# PAGE1-Power.net
KiCad netlist of a schematic drawn in Altium Designer
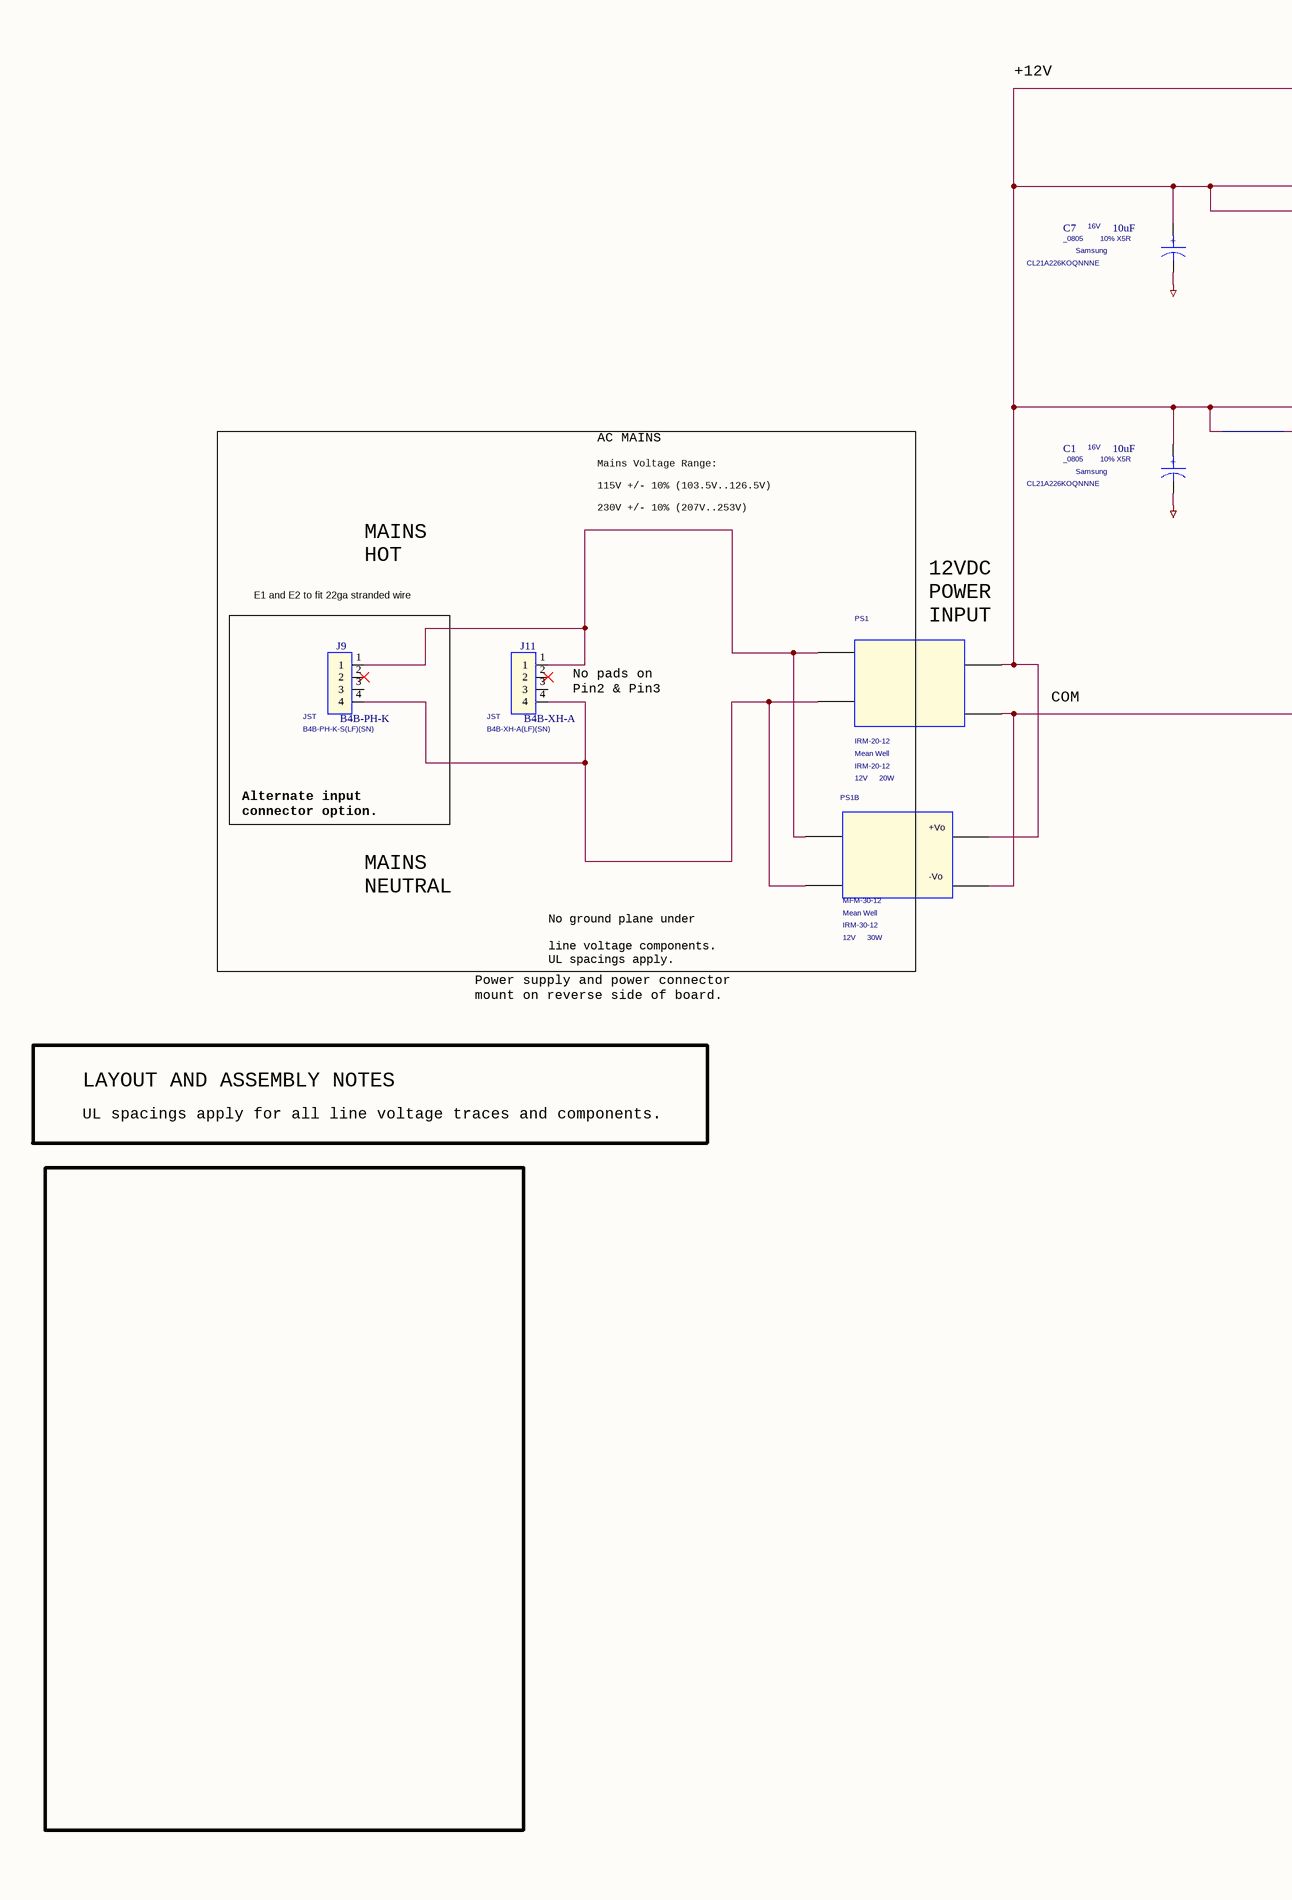
[diagram p0: PAGE1-Power.SchDoc, left]
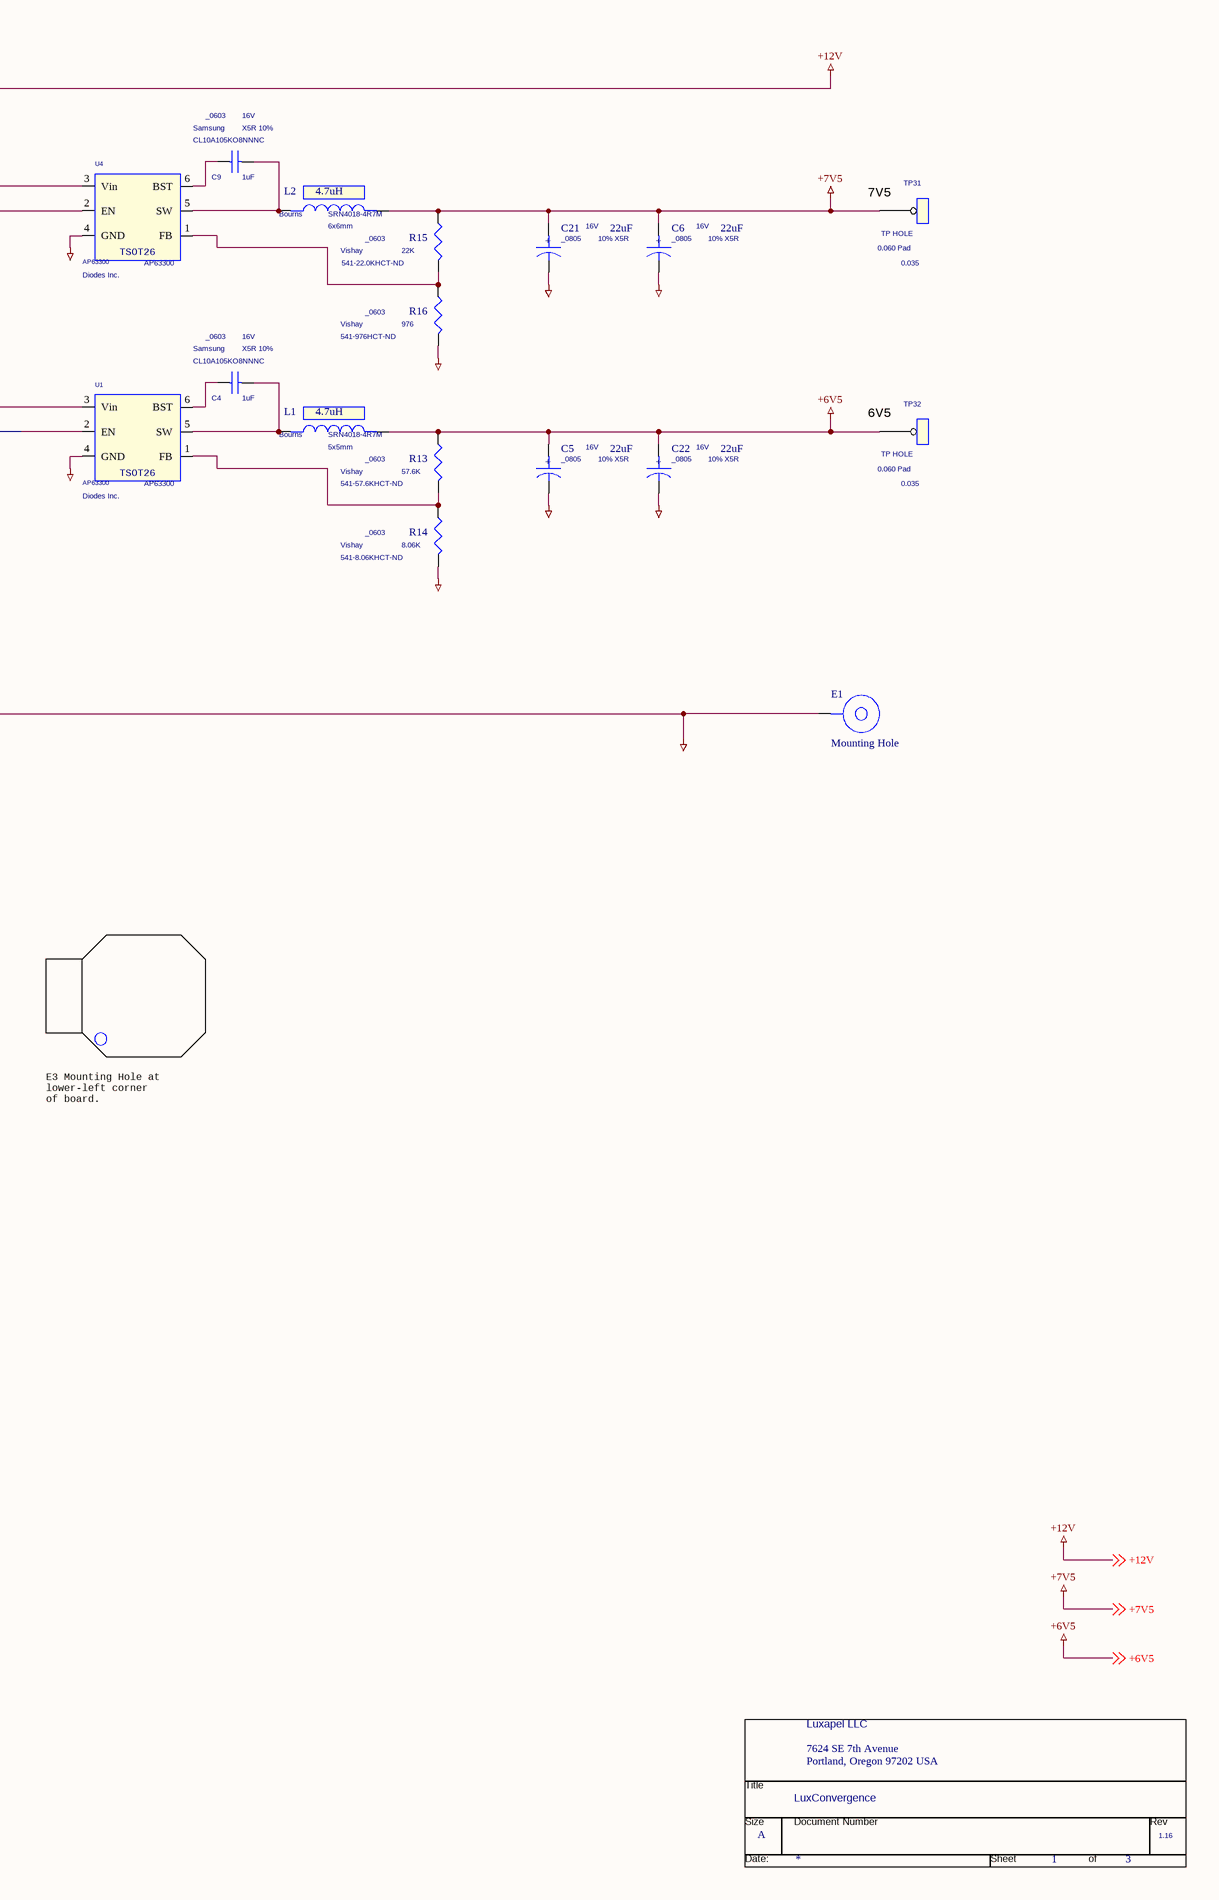
[diagram p1: PAGE1-Power.SchDoc, right]

(export (version "E")
  (design (tool "Eeschema 10.0.6"))
  (components
    (comp (ref "C1")
      (value "10uF")
      (footprint "_0805")
      (fields
        (field (name "PRECISION") "10% X5R")
        (field (name "VOLTAGE") "16V")
        (field (name "MFG") "Samsung")
        (field (name "P/N") "CL21A226KOQNNNE")
        (field (name "PCB FOOTPRINT") "_0805")
      )
      (libsource (lib "*") (part "CAPACITOR POL/SM"))
    )
    (comp (ref "C4")
      (value "1uF")
      (footprint "_0603")
      (fields
        (field (name "PRECISION") "X5R 10%")
        (field (name "VOLTAGE") "16V")
        (field (name "MFG") "Samsung")
        (field (name "P/N") "CL10A105KO8NNNC")
        (field (name "PCB FOOTPRINT") "_0603")
      )
      (libsource (lib "*") (part "CAPACITOR NON-POL"))
    )
    (comp (ref "C5")
      (value "22uF")
      (footprint "_0805")
      (fields
        (field (name "PCB FOOTPRINT") "_0805")
        (field (name "PRECISION") "10% X5R")
        (field (name "VOLTAGE") "16V")
        (field (name "MFG") "Samsung")
      )
      (libsource (lib "*") (part "CAPACITOR POL/SM"))
    )
    (comp (ref "C6")
      (value "22uF")
      (footprint "_0805")
      (fields
        (field (name "PCB FOOTPRINT") "_0805")
        (field (name "PRECISION") "10% X5R")
        (field (name "VOLTAGE") "16V")
        (field (name "MFG") "Samsung")
      )
      (libsource (lib "*") (part "CAPACITOR POL/SM"))
    )
    (comp (ref "C7")
      (value "10uF")
      (footprint "_0805")
      (fields
        (field (name "PRECISION") "10% X5R")
        (field (name "VOLTAGE") "16V")
        (field (name "MFG") "Samsung")
        (field (name "P/N") "CL21A226KOQNNNE")
        (field (name "PCB FOOTPRINT") "_0805")
      )
      (libsource (lib "*") (part "CAPACITOR POL/SM"))
    )
    (comp (ref "C9")
      (value "1uF")
      (footprint "_0603")
      (fields
        (field (name "PRECISION") "X5R 10%")
        (field (name "VOLTAGE") "16V")
        (field (name "MFG") "Samsung")
        (field (name "P/N") "CL10A105KO8NNNC")
        (field (name "PCB FOOTPRINT") "_0603")
      )
      (libsource (lib "*") (part "CAPACITOR NON-POL"))
    )
    (comp (ref "C21")
      (value "22uF")
      (footprint "_0805")
      (fields
        (field (name "PCB FOOTPRINT") "_0805")
        (field (name "MFG") "Samsung")
        (field (name "VOLTAGE") "16V")
        (field (name "PRECISION") "10% X5R")
      )
      (libsource (lib "*") (part "CAPACITOR POL/SM"))
    )
    (comp (ref "C22")
      (value "22uF")
      (footprint "_0805")
      (fields
        (field (name "PCB FOOTPRINT") "_0805")
        (field (name "MFG") "Samsung")
        (field (name "VOLTAGE") "16V")
        (field (name "PRECISION") "10% X5R")
      )
      (libsource (lib "*") (part "CAPACITOR POL/SM"))
    )
    (comp (ref "E1") (value "Mounting Hole") (footprint "MountingHole") (libsource (lib "*") (part "hole_0")))
    (comp (ref "J9")
      (value "B4B-PH-K")
      (footprint "SIP-4")
      (fields (field (name "P/N") "B4B-PH-K-S(LF)(SN)") (field (name "MFG") "JST"))
      (libsource (lib "*") (part "CON4_8"))
    )
    (comp (ref "J11")
      (value "B4B-XH-A")
      (footprint "SIP-4")
      (fields (field (name "P/N") "B4B-XH-A(LF)(SN)") (field (name "MFG") "JST"))
      (libsource (lib "*") (part "CON4_8"))
    )
    (comp (ref "L1")
      (value "4.7uH")
      (footprint "5x5mm")
      (fields
        (field (name "PCB FOOTPRINT") "5x5mm")
        (field (name "P/N") "SRN4018-4R7M")
        (field (name "MFG") "Bourns")
        (field (name "POWER") "1A")
      )
      (libsource (lib "*") (part "INDUCTOR FERRITE/SM"))
    )
    (comp (ref "L2")
      (value "4.7uH")
      (footprint "6x6mm")
      (fields
        (field (name "PCB FOOTPRINT") "6x6mm")
        (field (name "POWER") "1A")
        (field (name "MFG") "Bourns")
        (field (name "P/N") "SRN4018-4R7M")
      )
      (libsource (lib "*") (part "INDUCTOR FERRITE/SM"))
    )
    (comp (ref "PS1")
      (value "IRM-20-12")
      (footprint "ThruHolePS")
      (fields
        (field (name "MFG") "Mean Well")
        (field (name "P/N") "IRM-20-12")
        (field (name "VOLTAGE") "12V")
        (field (name "POWER") "20W")
      )
      (libsource (lib "*") (part "VOFM-5-5"))
    )
    (comp (ref "PS1B")
      (value "MFM-30-12")
      (footprint "THRUHOLEPS - duplicate")
      (fields
        (field (name "MFG") "Mean Well")
        (field (name "P/N") "IRM-30-12")
        (field (name "VOLTAGE") "12V")
        (field (name "POWER") "30W")
      )
      (libsource (lib "*") (part "VOFM-5-5_5"))
    )
    (comp (ref "R13")
      (value "57.6K")
      (footprint "_0603")
      (fields
        (field (name "PCB FOOTPRINT") "_0603")
        (field (name "VOLTAGE") "75V")
        (field (name "POWER") "0.10W")
        (field (name "P/N") "541-57.6KHCT-ND")
        (field (name "MFG") "Vishay")
      )
      (libsource (lib "*") (part "RESISTOR"))
    )
    (comp (ref "R14")
      (value "8.06K")
      (footprint "_0603")
      (fields
        (field (name "PCB FOOTPRINT") "_0603")
        (field (name "VOLTAGE") "75V")
        (field (name "POWER") "0.10W")
        (field (name "P/N") "541-8.06KHCT-ND")
        (field (name "MFG") "Vishay")
      )
      (libsource (lib "*") (part "RESISTOR"))
    )
    (comp (ref "R15")
      (value "22K")
      (footprint "_0603")
      (fields
        (field (name "PCB FOOTPRINT") "_0603")
        (field (name "VOLTAGE") "75V")
        (field (name "POWER") "0.10W")
        (field (name "P/N") "541-22.0KHCT-ND")
        (field (name "MFG") "Vishay")
      )
      (libsource (lib "*") (part "RESISTOR"))
    )
    (comp (ref "R16")
      (value "976")
      (footprint "_0603")
      (fields
        (field (name "PCB FOOTPRINT") "_0603")
        (field (name "VOLTAGE") "75V")
        (field (name "POWER") "0.10W")
        (field (name "P/N") "541-976HCT-ND")
        (field (name "MFG") "Vishay")
      )
      (libsource (lib "*") (part "RESISTOR"))
    )
    (comp (ref "TP31")
      (value "TP HOLE")
      (footprint "0.035")
      (fields (field (name "PCB FOOTPRINT") "0.035") (field (name "NOTES") "0.060 Pad"))
      (libsource (lib "*") (part "TEST POINT_1"))
    )
    (comp (ref "TP32")
      (value "TP HOLE")
      (footprint "0.035")
      (fields (field (name "PCB FOOTPRINT") "0.035") (field (name "NOTES") "0.060 Pad"))
      (libsource (lib "*") (part "TEST POINT_1"))
    )
    (comp (ref "U1")
      (value "AP63300")
      (footprint "SOIC-8")
      (fields (field (name "P/N") "AP63300") (field (name "MFG") "Diodes Inc."))
      (libsource (lib "LUXCON 1_24B_Library") (part "NCP3170_0_2"))
    )
    (comp (ref "U4")
      (value "AP63300")
      (footprint "SOIC-8")
      (fields (field (name "P/N") "AP63300") (field (name "MFG") "Diodes Inc."))
      (libsource (lib "LUXCON 1_24B_Library") (part "NCP3170_0_2"))
    )
  )
  (nets
    (net (code "1") (name "+6V5") (class "Default")
      (node (ref "C22") (pin "1") (pinfunction "1_1") (pintype "passive"))
      (node (ref "C5") (pin "1") (pinfunction "1_1") (pintype "passive"))
      (node (ref "L1") (pin "1") (pinfunction "1_1") (pintype "passive"))
      (node (ref "R13") (pin "1") (pinfunction "1_1") (pintype "passive"))
      (node (ref "TP32") (pin "1") (pinfunction "1_1") (pintype "passive"))
    )
    (net (code "2") (name "+7V5") (class "Default")
      (node (ref "C21") (pin "1") (pinfunction "1_1") (pintype "passive"))
      (node (ref "C6") (pin "1") (pinfunction "1_1") (pintype "passive"))
      (node (ref "L2") (pin "1") (pinfunction "1_1") (pintype "passive"))
      (node (ref "R15") (pin "1") (pinfunction "1_1") (pintype "passive"))
      (node (ref "TP31") (pin "1") (pinfunction "1_1") (pintype "passive"))
    )
    (net (code "3") (name "+12V") (class "Default")
      (node (ref "C1") (pin "1") (pinfunction "1_1") (pintype "passive"))
      (node (ref "C7") (pin "1") (pinfunction "1_1") (pintype "passive"))
      (node (ref "PS1") (pin "+Vo") (pinfunction "+Vo_+Vo") (pintype "passive"))
      (node (ref "PS1B") (pin "+Vo") (pinfunction "+Vo_+Vo") (pintype "passive"))
      (node (ref "U1") (pin "2") (pinfunction "EN_2") (pintype "passive"))
      (node (ref "U1") (pin "3") (pinfunction "Vin_3") (pintype "power_in"))
      (node (ref "U4") (pin "2") (pinfunction "EN_2") (pintype "passive"))
      (node (ref "U4") (pin "3") (pinfunction "Vin_3") (pintype "power_in"))
    )
    (net (code "4") (name "GND_POWER.global") (class "Default")
      (node (ref "C1") (pin "2") (pinfunction "2_2") (pintype "passive"))
      (node (ref "C21") (pin "2") (pinfunction "2_2") (pintype "passive"))
      (node (ref "C22") (pin "2") (pinfunction "2_2") (pintype "passive"))
      (node (ref "C5") (pin "2") (pinfunction "2_2") (pintype "passive"))
      (node (ref "C6") (pin "2") (pinfunction "2_2") (pintype "passive"))
      (node (ref "C7") (pin "2") (pinfunction "2_2") (pintype "passive"))
      (node (ref "E1") (pin "1") (pinfunction "1_1") (pintype "passive"))
      (node (ref "PS1") (pin "-Vo") (pinfunction "-Vo_-Vo") (pintype "passive"))
      (node (ref "PS1B") (pin "-Vo") (pinfunction "-Vo_-Vo") (pintype "passive"))
      (node (ref "R14") (pin "2") (pinfunction "2_2") (pintype "passive"))
      (node (ref "R16") (pin "2") (pinfunction "2_2") (pintype "passive"))
      (node (ref "U1") (pin "4") (pinfunction "GND_4") (pintype "power_in"))
      (node (ref "U4") (pin "4") (pinfunction "GND_4") (pintype "power_in"))
    )
    (net (code "5") (name "Net-(J11-Pad1)") (class "Default")
      (node (ref "J11") (pin "1") (pinfunction "1_1") (pintype "passive"))
      (node (ref "J9") (pin "1") (pinfunction "1_1") (pintype "passive"))
      (node (ref "PS1") (pin "ACL") (pinfunction "ACL_ACL") (pintype "passive"))
      (node (ref "PS1B") (pin "ACN") (pinfunction "ACN_ACN") (pintype "passive"))
    )
    (net (code "6") (name "Net-(J11-Pad4)") (class "Default")
      (node (ref "J11") (pin "4") (pinfunction "4_4") (pintype "passive"))
      (node (ref "J9") (pin "4") (pinfunction "4_4") (pintype "passive"))
      (node (ref "PS1") (pin "ACN") (pinfunction "ACN_ACN") (pintype "passive"))
      (node (ref "PS1B") (pin "ACL") (pinfunction "ACL_ACL") (pintype "passive"))
    )
    (net (code "7") (name "Net-(U1-BST)") (class "Default")
      (node (ref "C4") (pin "1") (pinfunction "1_1") (pintype "passive"))
      (node (ref "U1") (pin "6") (pinfunction "BST_6") (pintype "power_in"))
    )
    (net (code "8") (name "Net-(U1-FB)") (class "Default")
      (node (ref "R13") (pin "2") (pinfunction "2_2") (pintype "passive"))
      (node (ref "R14") (pin "1") (pinfunction "1_1") (pintype "passive"))
      (node (ref "U1") (pin "1") (pinfunction "FB_1") (pintype "passive"))
    )
    (net (code "9") (name "Net-(U1-SW)") (class "Default")
      (node (ref "C4") (pin "2") (pinfunction "2_2") (pintype "passive"))
      (node (ref "L1") (pin "2") (pinfunction "2_2") (pintype "passive"))
      (node (ref "U1") (pin "5") (pinfunction "SW_5") (pintype "passive"))
    )
    (net (code "10") (name "Net-(U4-BST)") (class "Default")
      (node (ref "C9") (pin "1") (pinfunction "1_1") (pintype "passive"))
      (node (ref "U4") (pin "6") (pinfunction "BST_6") (pintype "power_in"))
    )
    (net (code "11") (name "Net-(U4-FB)") (class "Default")
      (node (ref "R15") (pin "2") (pinfunction "2_2") (pintype "passive"))
      (node (ref "R16") (pin "1") (pinfunction "1_1") (pintype "passive"))
      (node (ref "U4") (pin "1") (pinfunction "FB_1") (pintype "passive"))
    )
    (net (code "12") (name "Net-(U4-SW)") (class "Default")
      (node (ref "C9") (pin "2") (pinfunction "2_2") (pintype "passive"))
      (node (ref "L2") (pin "2") (pinfunction "2_2") (pintype "passive"))
      (node (ref "U4") (pin "5") (pinfunction "SW_5") (pintype "passive"))
    )
    (net (code "13") (name "unconnected-(J9-Pad2)") (class "Default")
      (node (ref "J9") (pin "2") (pinfunction "2_2") (pintype "passive+no_connect"))
    )
    (net (code "14") (name "unconnected-(J9-Pad3)") (class "Default")
      (node (ref "J9") (pin "3") (pinfunction "3_3") (pintype "passive"))
    )
    (net (code "15") (name "unconnected-(J11-Pad2)") (class "Default")
      (node (ref "J11") (pin "2") (pinfunction "2_2") (pintype "passive+no_connect"))
    )
    (net (code "16") (name "unconnected-(J11-Pad3)") (class "Default")
      (node (ref "J11") (pin "3") (pinfunction "3_3") (pintype "passive"))
    )
  )
)
